# MotorCell_noPow.net
KiCad netlist of a schematic drawn in Altium Designer
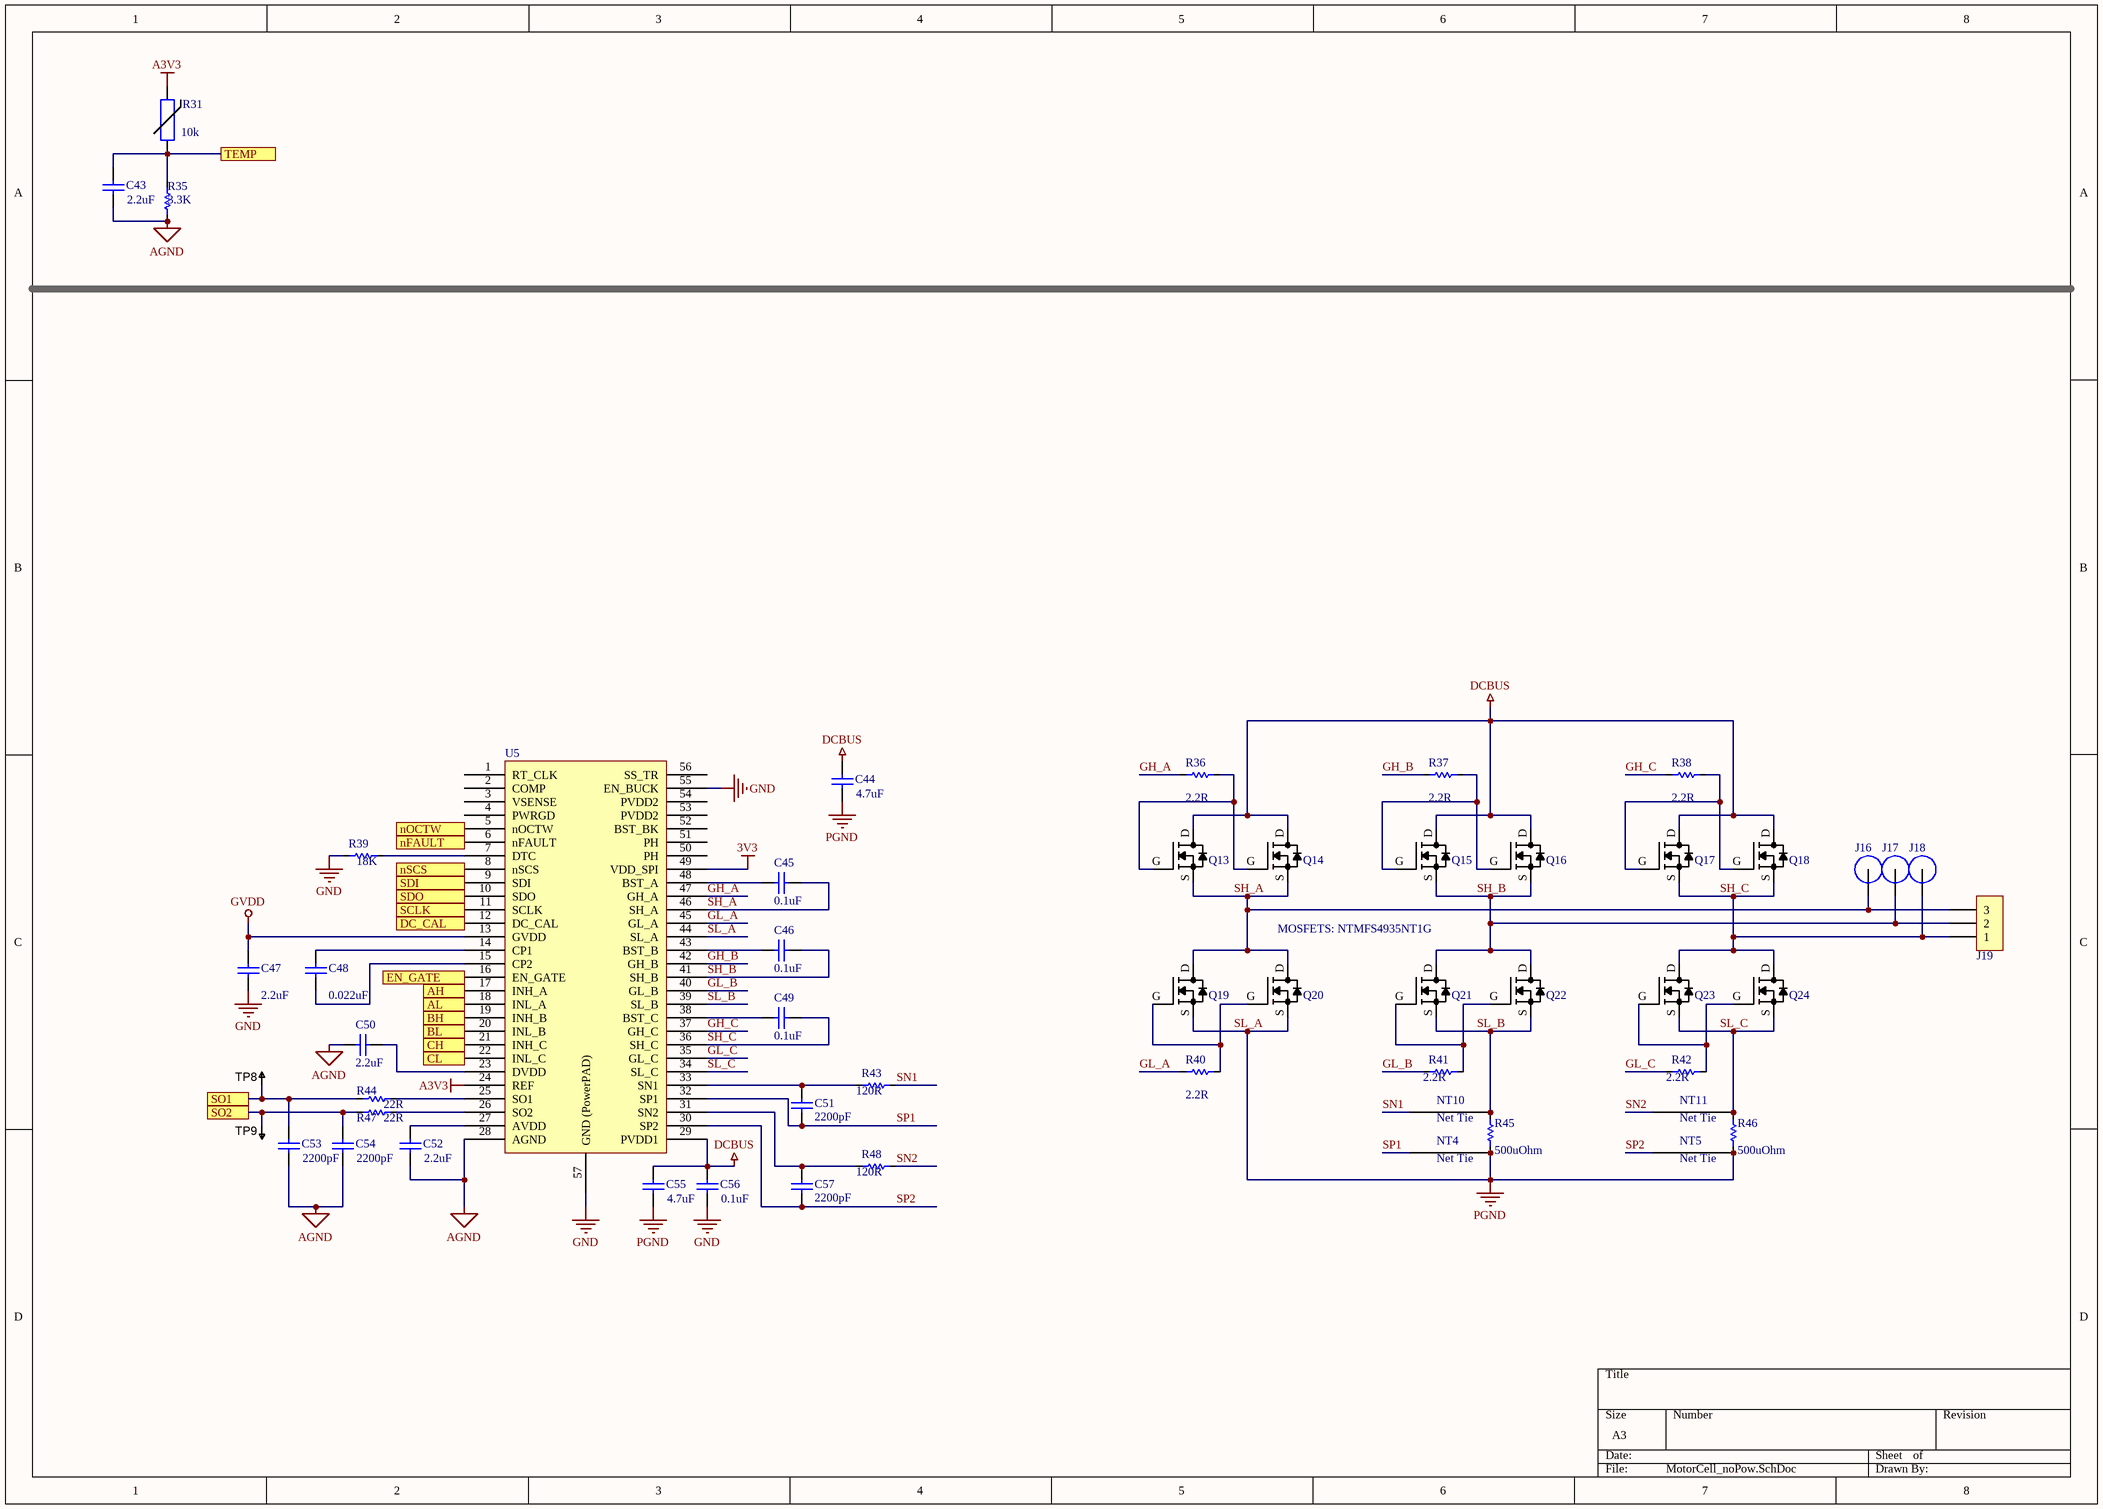
[diagram p0: MotorCell_noPow.SchDoc]

(export (version "E")
  (design (tool "Eeschema 10.0.6"))
  (components
    (comp (ref "C43")
      (value "2.2uF")
      (footprint "C0603")
      (description "Capacitor")
      (fields (field (name "Comment") "Cap") (field (name "PUBLISHER") "Altium Limited"))
      (libsource (lib "Component footprints") (part "Cap"))
    )
    (comp (ref "C44")
      (value "4.7uF")
      (footprint "C0805")
      (description "Capacitor")
      (fields (field (name "Comment") "Cap") (field (name "PUBLISHER") "Altium Limited"))
      (libsource (lib "Component footprints") (part "Cap"))
    )
    (comp (ref "C45")
      (value "0.1uF")
      (footprint "C0603")
      (description "CAP CER 0.1UF 50V X7R 0603")
      (fields (field (name "Comment") "Cap") (field (name "PUBLISHER") "Altium Limited"))
      (libsource (lib "Component footprints") (part "Cap"))
    )
    (comp (ref "C46")
      (value "0.1uF")
      (footprint "C0603")
      (description "CAP CER 0.1UF 50V X7R 0603")
      (fields (field (name "Comment") "Cap") (field (name "PUBLISHER") "Altium Limited"))
      (libsource (lib "Component footprints") (part "Cap"))
    )
    (comp (ref "C47")
      (value "2.2uF")
      (footprint "C0603")
      (description "Capacitor")
      (fields (field (name "Comment") "Cap") (field (name "PUBLISHER") "Altium Limited"))
      (libsource (lib "Component footprints") (part "Cap"))
    )
    (comp (ref "C48")
      (value "0.022uF")
      (footprint "C0603")
      (description "CAP CER 0.022UF 50V X7R 0603")
      (fields (field (name "Comment") "Cap") (field (name "PUBLISHER") "Altium Limited"))
      (libsource (lib "Component footprints") (part "Cap"))
    )
    (comp (ref "C49")
      (value "0.1uF")
      (footprint "C0603")
      (description "CAP CER 0.1UF 50V X7R 0603")
      (fields (field (name "Comment") "Cap") (field (name "PUBLISHER") "Altium Limited"))
      (libsource (lib "Component footprints") (part "Cap"))
    )
    (comp (ref "C50")
      (value "2.2uF")
      (footprint "C0603")
      (description "Capacitor")
      (fields (field (name "Comment") "Cap") (field (name "PUBLISHER") "Altium Limited"))
      (libsource (lib "Component footprints") (part "Cap"))
    )
    (comp (ref "C51")
      (value "2200pF")
      (footprint "C0603")
      (description "CAP CER 2200PF 50V NP0 0603")
      (fields (field (name "Comment") "Cap") (field (name "PUBLISHER") "Altium Limited"))
      (libsource (lib "Component footprints") (part "Cap"))
    )
    (comp (ref "C52")
      (value "2.2uF")
      (footprint "C0603")
      (description "CAP CER 2.2UF 16V X5R 0603")
      (fields (field (name "Comment") "Cap") (field (name "PUBLISHER") "Altium Limited"))
      (libsource (lib "Component footprints") (part "Cap"))
    )
    (comp (ref "C53")
      (value "2200pF")
      (footprint "C0603")
      (description "CAP CER 2200PF 50V NP0 0603")
      (fields (field (name "Comment") "Cap") (field (name "PUBLISHER") "Altium Limited"))
      (libsource (lib "Component footprints") (part "Cap"))
    )
    (comp (ref "C54")
      (value "2200pF")
      (footprint "C0603")
      (description "CAP CER 2200PF 50V NP0 0603")
      (fields (field (name "Comment") "Cap") (field (name "PUBLISHER") "Altium Limited"))
      (libsource (lib "Component footprints") (part "Cap"))
    )
    (comp (ref "C55")
      (value "4.7uF")
      (footprint "C0805")
      (description "CAP CER 4.7UF 35V X5R 0805")
      (fields (field (name "Comment") "Cap") (field (name "PUBLISHER") "Altium Limited"))
      (libsource (lib "Component footprints") (part "Cap"))
    )
    (comp (ref "C56")
      (value "0.1uF")
      (footprint "C0603")
      (description "CAP CER 0.1UF 50V X7R 0603")
      (fields (field (name "Comment") "Cap") (field (name "PUBLISHER") "Altium Limited"))
      (libsource (lib "Component footprints") (part "Cap"))
    )
    (comp (ref "C57")
      (value "2200pF")
      (footprint "C0603")
      (description "CAP CER 2200PF 50V NP0 0603")
      (fields (field (name "Comment") "Cap") (field (name "PUBLISHER") "Altium Limited"))
      (libsource (lib "Component footprints") (part "Cap"))
    )
    (comp (ref "J16")
      (value "~")
      (footprint "M3 Spade Hole")
      (description "M3 Spade Terminal")
      (libsource (lib "CustomComponents") (part "M3 Spade Terminal"))
    )
    (comp (ref "J17")
      (value "~")
      (footprint "M3 Spade Hole")
      (description "M3 Spade Terminal")
      (libsource (lib "CustomComponents") (part "M3 Spade Terminal"))
    )
    (comp (ref "J18")
      (value "~")
      (footprint "M3 Spade Hole")
      (description "M3 Spade Terminal")
      (libsource (lib "CustomComponents") (part "M3 Spade Terminal"))
    )
    (comp (ref "J19")
      (value "1704936")
      (footprint "1704936")
      (description "CONN TERM BLOCK 3POS 7.62MM")
      (fields (field (name "MANUFACTURER") "Phoenix Contact") (field (name "VOLTAGE") "300V"))
      (libsource (lib "CustomComponents") (part "1704936"))
    )
    (comp (ref "NT4")
      (value "0.25mm")
      (footprint "NetTie_0.25mm")
      (libsource (lib "CustomComponents") (part "NetTie_0.25mm"))
    )
    (comp (ref "NT5")
      (value "0.25mm")
      (footprint "NetTie_0.25mm")
      (libsource (lib "CustomComponents") (part "NetTie_0.25mm"))
    )
    (comp (ref "NT10")
      (value "0.25mm")
      (footprint "NetTie_0.25mm")
      (libsource (lib "CustomComponents") (part "NetTie_0.25mm"))
    )
    (comp (ref "NT11")
      (value "0.25mm")
      (footprint "NetTie_0.25mm")
      (libsource (lib "CustomComponents") (part "NetTie_0.25mm"))
    )
    (comp (ref "Q13")
      (value "~")
      (footprint "SO8FL")
      (description "MOSFET N-CH 30V 13A SO8FL")
      (fields
        (field (name "MANUFACTURER") "ON Semiconductor")
        (field (name "MANUFACTURER PART NUMBER") "NTMFS4935NT1G")
      )
      (libsource (lib "CustomComponents") (part "NTMFS4935NT1G"))
    )
    (comp (ref "Q14")
      (value "FILL_FOOTPRINT")
      (footprint "SO8FL_FILL")
      (description "MOSFET N-CH 30V 13A SO8FL")
      (fields
        (field (name "MANUFACTURER") "ON Semiconductor")
        (field (name "MANUFACTURER PART NUMBER") "NTMFS4935NT1G")
      )
      (libsource (lib "CustomComponents") (part "NTMFS4935NT1G"))
    )
    (comp (ref "Q15")
      (value "~")
      (footprint "SO8FL")
      (description "MOSFET N-CH 30V 13A SO8FL")
      (fields
        (field (name "MANUFACTURER") "ON Semiconductor")
        (field (name "MANUFACTURER PART NUMBER") "NTMFS4935NT1G")
      )
      (libsource (lib "CustomComponents") (part "NTMFS4935NT1G"))
    )
    (comp (ref "Q16")
      (value "FILL_FOOTPRINT")
      (footprint "SO8FL_FILL")
      (description "MOSFET N-CH 30V 13A SO8FL")
      (fields
        (field (name "MANUFACTURER") "ON Semiconductor")
        (field (name "MANUFACTURER PART NUMBER") "NTMFS4935NT1G")
      )
      (libsource (lib "CustomComponents") (part "NTMFS4935NT1G"))
    )
    (comp (ref "Q17")
      (value "~")
      (footprint "SO8FL")
      (description "MOSFET N-CH 30V 13A SO8FL")
      (fields
        (field (name "MANUFACTURER") "ON Semiconductor")
        (field (name "MANUFACTURER PART NUMBER") "NTMFS4935NT1G")
      )
      (libsource (lib "CustomComponents") (part "NTMFS4935NT1G"))
    )
    (comp (ref "Q18")
      (value "FILL_FOOTPRINT")
      (footprint "SO8FL_FILL")
      (description "MOSFET N-CH 30V 13A SO8FL")
      (fields
        (field (name "MANUFACTURER") "ON Semiconductor")
        (field (name "MANUFACTURER PART NUMBER") "NTMFS4935NT1G")
      )
      (libsource (lib "CustomComponents") (part "NTMFS4935NT1G"))
    )
    (comp (ref "Q19")
      (value "~")
      (footprint "SO8FL")
      (description "MOSFET N-CH 30V 13A SO8FL")
      (fields
        (field (name "MANUFACTURER") "ON Semiconductor")
        (field (name "MANUFACTURER PART NUMBER") "NTMFS4935NT1G")
      )
      (libsource (lib "CustomComponents") (part "NTMFS4935NT1G"))
    )
    (comp (ref "Q20")
      (value "~")
      (footprint "SO8FL")
      (description "MOSFET N-CH 30V 13A SO8FL")
      (fields
        (field (name "MANUFACTURER") "ON Semiconductor")
        (field (name "MANUFACTURER PART NUMBER") "NTMFS4935NT1G")
      )
      (libsource (lib "CustomComponents") (part "NTMFS4935NT1G"))
    )
    (comp (ref "Q21")
      (value "~")
      (footprint "SO8FL")
      (description "MOSFET N-CH 30V 13A SO8FL")
      (fields
        (field (name "MANUFACTURER") "ON Semiconductor")
        (field (name "MANUFACTURER PART NUMBER") "NTMFS4935NT1G")
      )
      (libsource (lib "CustomComponents") (part "NTMFS4935NT1G"))
    )
    (comp (ref "Q22")
      (value "~")
      (footprint "SO8FL")
      (description "MOSFET N-CH 30V 13A SO8FL")
      (fields
        (field (name "MANUFACTURER") "ON Semiconductor")
        (field (name "MANUFACTURER PART NUMBER") "NTMFS4935NT1G")
      )
      (libsource (lib "CustomComponents") (part "NTMFS4935NT1G"))
    )
    (comp (ref "Q23")
      (value "~")
      (footprint "SO8FL")
      (description "MOSFET N-CH 30V 13A SO8FL")
      (fields
        (field (name "MANUFACTURER") "ON Semiconductor")
        (field (name "MANUFACTURER PART NUMBER") "NTMFS4935NT1G")
      )
      (libsource (lib "CustomComponents") (part "NTMFS4935NT1G"))
    )
    (comp (ref "Q24")
      (value "~")
      (footprint "SO8FL")
      (description "MOSFET N-CH 30V 13A SO8FL")
      (fields
        (field (name "MANUFACTURER") "ON Semiconductor")
        (field (name "MANUFACTURER PART NUMBER") "NTMFS4935NT1G")
      )
      (libsource (lib "CustomComponents") (part "NTMFS4935NT1G"))
    )
    (comp (ref "R31")
      (value "10k")
      (footprint "RESC1005X40N")
      (description "THERMISTOR 10K OHM NTC 0402 SMD")
      (libsource (lib "CustomComponents") (part "NCP15XH103F03RC"))
    )
    (comp (ref "R35")
      (value "3.3K")
      (footprint "R0603")
      (description "Resistor")
      (fields (field (name "Comment") "Res") (field (name "PUBLISHER") "Altium Limited"))
      (libsource (lib "Component footprints") (part "Res"))
    )
    (comp (ref "R36")
      (value "2.2R")
      (footprint "R0603")
      (description "Resistor")
      (fields (field (name "Comment") "Res") (field (name "PUBLISHER") "Altium Limited"))
      (libsource (lib "Component footprints") (part "Res"))
    )
    (comp (ref "R37")
      (value "2.2R")
      (footprint "R0603")
      (description "Resistor")
      (fields (field (name "Comment") "Res") (field (name "PUBLISHER") "Altium Limited"))
      (libsource (lib "Component footprints") (part "Res"))
    )
    (comp (ref "R38")
      (value "2.2R")
      (footprint "R0603")
      (description "Resistor")
      (fields (field (name "Comment") "Res") (field (name "PUBLISHER") "Altium Limited"))
      (libsource (lib "Component footprints") (part "Res"))
    )
    (comp (ref "R39")
      (value "18K")
      (footprint "R0603")
      (description "Resistor")
      (fields (field (name "Comment") "Res") (field (name "PUBLISHER") "Altium Limited"))
      (libsource (lib "Component footprints") (part "Res"))
    )
    (comp (ref "R40")
      (value "2.2R")
      (footprint "R0603")
      (description "Resistor")
      (fields (field (name "Comment") "Res") (field (name "PUBLISHER") "Altium Limited"))
      (libsource (lib "Component footprints") (part "Res"))
    )
    (comp (ref "R41")
      (value "2.2R")
      (footprint "R0603")
      (description "Resistor")
      (fields (field (name "Comment") "Res") (field (name "PUBLISHER") "Altium Limited"))
      (libsource (lib "Component footprints") (part "Res"))
    )
    (comp (ref "R42")
      (value "2.2R")
      (footprint "R0603")
      (description "Resistor")
      (fields (field (name "Comment") "Res") (field (name "PUBLISHER") "Altium Limited"))
      (libsource (lib "Component footprints") (part "Res"))
    )
    (comp (ref "R43")
      (value "120R")
      (footprint "R0603")
      (description "Resistor")
      (fields (field (name "Comment") "Res") (field (name "PUBLISHER") "Altium Limited"))
      (libsource (lib "Component footprints") (part "Res"))
    )
    (comp (ref "R44")
      (value "22R")
      (footprint "R0603")
      (description "Resistor")
      (fields (field (name "Comment") "Res") (field (name "PUBLISHER") "Altium Limited"))
      (libsource (lib "Component footprints") (part "Res"))
    )
    (comp (ref "R45")
      (value "500uOhm")
      (footprint "R2512")
      (description "RES SMD 0.0005 OHM 1% 3W 2512")
      (fields (field (name "Comment") "Res") (field (name "PUBLISHER") "Altium Limited"))
      (libsource (lib "Component footprints") (part "Res"))
    )
    (comp (ref "R46")
      (value "500uOhm")
      (footprint "R2512")
      (description "RES SMD 0.0005 OHM 1% 3W 2512")
      (fields (field (name "Comment") "Res") (field (name "PUBLISHER") "Altium Limited"))
      (libsource (lib "Component footprints") (part "Res"))
    )
    (comp (ref "R47")
      (value "22R")
      (footprint "R0603")
      (description "Resistor")
      (fields (field (name "Comment") "Res") (field (name "PUBLISHER") "Altium Limited"))
      (libsource (lib "Component footprints") (part "Res"))
    )
    (comp (ref "R48")
      (value "120R")
      (footprint "R0603")
      (description "Resistor")
      (fields (field (name "Comment") "Res") (field (name "PUBLISHER") "Altium Limited"))
      (libsource (lib "Component footprints") (part "Res"))
    )
    (comp (ref "TP8")
      (value "TESTPOINT")
      (footprint "TP-R30")
      (description "SMD test pin")
      (libsource (lib "PBL - Test Points") (part "TESTPOINT"))
    )
    (comp (ref "TP9")
      (value "TESTPOINT")
      (footprint "TP-R30")
      (description "SMD test pin")
      (libsource (lib "PBL - Test Points") (part "TESTPOINT"))
    )
    (comp (ref "U5")
      (value "~")
      (footprint "TSSOP50P810X120_HS-57N")
      (description "MOTOR DRIVER, 3PH, 56HTSSOP")
      (libsource (lib "CustomComponents") (part "DRV8301"))
    )
  )
  (nets
    (net (code "1") (name "/AH") (class "Default")
      (node (ref "U5") (pin "17") (pinfunction "INH_A_17") (pintype "passive"))
    )
    (net (code "2") (name "/AL") (class "Default")
      (node (ref "U5") (pin "18") (pinfunction "INL_A_18") (pintype "passive"))
    )
    (net (code "3") (name "/BH") (class "Default")
      (node (ref "U5") (pin "19") (pinfunction "INH_B_19") (pintype "passive"))
    )
    (net (code "4") (name "/BL") (class "Default")
      (node (ref "U5") (pin "20") (pinfunction "INL_B_20") (pintype "passive"))
    )
    (net (code "5") (name "/CH") (class "Default")
      (node (ref "U5") (pin "21") (pinfunction "INH_C_21") (pintype "passive"))
    )
    (net (code "6") (name "/CL") (class "Default")
      (node (ref "U5") (pin "22") (pinfunction "INL_C_22") (pintype "passive"))
    )
    (net (code "7") (name "/DC_CAL") (class "Default")
      (node (ref "U5") (pin "12") (pinfunction "DC_CAL_12") (pintype "passive"))
    )
    (net (code "8") (name "/EN_GATE") (class "Default")
      (node (ref "U5") (pin "16") (pinfunction "EN_GATE_16") (pintype "passive"))
    )
    (net (code "9") (name "/GH_A") (class "Default")
      (node (ref "R36") (pin "2") (pinfunction "2_2") (pintype "passive"))
      (node (ref "U5") (pin "47") (pinfunction "GH_A_47") (pintype "passive"))
    )
    (net (code "10") (name "/GH_B") (class "Default")
      (node (ref "R37") (pin "2") (pinfunction "2_2") (pintype "passive"))
      (node (ref "U5") (pin "42") (pinfunction "GH_B_42") (pintype "passive"))
    )
    (net (code "11") (name "/GH_C") (class "Default")
      (node (ref "R38") (pin "2") (pinfunction "2_2") (pintype "passive"))
      (node (ref "U5") (pin "37") (pinfunction "GH_C_37") (pintype "passive"))
    )
    (net (code "12") (name "/GL_A") (class "Default")
      (node (ref "R40") (pin "2") (pinfunction "2_2") (pintype "passive"))
      (node (ref "U5") (pin "45") (pinfunction "GL_A_45") (pintype "passive"))
    )
    (net (code "13") (name "/GL_B") (class "Default")
      (node (ref "R41") (pin "2") (pinfunction "2_2") (pintype "passive"))
      (node (ref "U5") (pin "40") (pinfunction "GL_B_40") (pintype "passive"))
    )
    (net (code "14") (name "/GL_C") (class "Default")
      (node (ref "R42") (pin "2") (pinfunction "2_2") (pintype "passive"))
      (node (ref "U5") (pin "35") (pinfunction "GL_C_35") (pintype "passive"))
    )
    (net (code "15") (name "/SCLK") (class "Default")
      (node (ref "U5") (pin "11") (pinfunction "SCLK_11") (pintype "passive"))
    )
    (net (code "16") (name "/SDI") (class "Default")
      (node (ref "U5") (pin "9") (pinfunction "SDI_9") (pintype "passive"))
    )
    (net (code "17") (name "/SDO") (class "Default")
      (node (ref "U5") (pin "10") (pinfunction "SDO_10") (pintype "passive"))
    )
    (net (code "18") (name "/SH_A") (class "Default")
      (node (ref "C45") (pin "1") (pinfunction "1_1") (pintype "passive"))
      (node (ref "J16") (pin "1") (pinfunction "1_1") (pintype "passive"))
      (node (ref "J19") (pin "3") (pinfunction "3_3") (pintype "passive"))
      (node (ref "Q13") (pin "S") (pinfunction "S_S") (pintype "passive"))
      (node (ref "Q14") (pin "S") (pinfunction "S_S") (pintype "passive"))
      (node (ref "Q19") (pin "D") (pinfunction "D_D") (pintype "passive"))
      (node (ref "Q20") (pin "D") (pinfunction "D_D") (pintype "passive"))
      (node (ref "U5") (pin "46") (pinfunction "SH_A_46") (pintype "passive"))
    )
    (net (code "19") (name "/SH_B") (class "Default")
      (node (ref "C46") (pin "1") (pinfunction "1_1") (pintype "passive"))
      (node (ref "J17") (pin "1") (pinfunction "1_1") (pintype "passive"))
      (node (ref "J19") (pin "2") (pinfunction "2_2") (pintype "passive"))
      (node (ref "Q15") (pin "S") (pinfunction "S_S") (pintype "passive"))
      (node (ref "Q16") (pin "S") (pinfunction "S_S") (pintype "passive"))
      (node (ref "Q21") (pin "D") (pinfunction "D_D") (pintype "passive"))
      (node (ref "Q22") (pin "D") (pinfunction "D_D") (pintype "passive"))
      (node (ref "U5") (pin "41") (pinfunction "SH_B_41") (pintype "passive"))
    )
    (net (code "20") (name "/SH_C") (class "Default")
      (node (ref "C49") (pin "1") (pinfunction "1_1") (pintype "passive"))
      (node (ref "J18") (pin "1") (pinfunction "1_1") (pintype "passive"))
      (node (ref "J19") (pin "1") (pinfunction "1_1") (pintype "passive"))
      (node (ref "Q17") (pin "S") (pinfunction "S_S") (pintype "passive"))
      (node (ref "Q18") (pin "S") (pinfunction "S_S") (pintype "passive"))
      (node (ref "Q23") (pin "D") (pinfunction "D_D") (pintype "passive"))
      (node (ref "Q24") (pin "D") (pinfunction "D_D") (pintype "passive"))
      (node (ref "U5") (pin "36") (pinfunction "SH_C_36") (pintype "passive"))
    )
    (net (code "21") (name "/SL_B") (class "Default")
      (node (ref "NT10") (pin "2") (pintype "passive"))
      (node (ref "Q21") (pin "S") (pinfunction "S_S") (pintype "passive"))
      (node (ref "Q22") (pin "S") (pinfunction "S_S") (pintype "passive"))
      (node (ref "R45") (pin "2") (pinfunction "2_2") (pintype "passive"))
      (node (ref "U5") (pin "39") (pinfunction "SL_B_39") (pintype "passive"))
    )
    (net (code "22") (name "/SL_C") (class "Default")
      (node (ref "NT11") (pin "2") (pintype "passive"))
      (node (ref "Q23") (pin "S") (pinfunction "S_S") (pintype "passive"))
      (node (ref "Q24") (pin "S") (pinfunction "S_S") (pintype "passive"))
      (node (ref "R46") (pin "2") (pinfunction "2_2") (pintype "passive"))
      (node (ref "U5") (pin "34") (pinfunction "SL_C_34") (pintype "passive"))
    )
    (net (code "23") (name "/SN1") (class "Default")
      (node (ref "NT10") (pin "1") (pintype "passive"))
      (node (ref "R43") (pin "2") (pinfunction "2_2") (pintype "passive"))
    )
    (net (code "24") (name "/SN2") (class "Default")
      (node (ref "NT11") (pin "1") (pintype "passive"))
      (node (ref "R48") (pin "2") (pinfunction "2_2") (pintype "passive"))
    )
    (net (code "25") (name "/SO1") (class "Default")
      (node (ref "C53") (pin "2") (pinfunction "2_2") (pintype "passive"))
      (node (ref "R44") (pin "1") (pinfunction "1_1") (pintype "passive"))
      (node (ref "TP8") (pin "1") (pintype "passive"))
    )
    (net (code "26") (name "/SO2") (class "Default")
      (node (ref "C54") (pin "2") (pinfunction "2_2") (pintype "passive"))
      (node (ref "R47") (pin "1") (pinfunction "1_1") (pintype "passive"))
      (node (ref "TP9") (pin "1") (pintype "passive"))
    )
    (net (code "27") (name "/SP1") (class "Default")
      (node (ref "C51") (pin "2") (pinfunction "2_2") (pintype "passive"))
      (node (ref "NT4") (pin "1") (pintype "passive"))
      (node (ref "U5") (pin "32") (pinfunction "SP1_32") (pintype "passive"))
    )
    (net (code "28") (name "/SP2") (class "Default")
      (node (ref "C57") (pin "2") (pinfunction "2_2") (pintype "passive"))
      (node (ref "NT5") (pin "1") (pintype "passive"))
      (node (ref "U5") (pin "30") (pinfunction "SP2_30") (pintype "passive"))
    )
    (net (code "29") (name "/TEMP") (class "Default")
      (node (ref "C43") (pin "2") (pinfunction "2_2") (pintype "passive"))
      (node (ref "R31") (pin "1") (pinfunction "0_1") (pintype "passive"))
      (node (ref "R35") (pin "2") (pinfunction "2_2") (pintype "passive"))
    )
    (net (code "30") (name "/nFAULT") (class "Default")
      (node (ref "U5") (pin "6") (pinfunction "nFAULT_6") (pintype "passive"))
    )
    (net (code "31") (name "/nOCTW") (class "Default")
      (node (ref "U5") (pin "5") (pinfunction "nOCTW_5") (pintype "passive"))
    )
    (net (code "32") (name "/nSCS") (class "Default")
      (node (ref "U5") (pin "8") (pinfunction "nSCS_8") (pintype "passive"))
    )
    (net (code "33") (name "3V3") (class "Default")
      (node (ref "U5") (pin "49") (pinfunction "VDD_SPI_49") (pintype "passive"))
    )
    (net (code "34") (name "A3V3") (class "Default")
      (node (ref "R31") (pin "2") (pinfunction "0_2") (pintype "passive"))
      (node (ref "U5") (pin "24") (pinfunction "REF_24") (pintype "passive"))
    )
    (net (code "35") (name "AGND") (class "Default")
      (node (ref "C43") (pin "1") (pinfunction "1_1") (pintype "passive"))
      (node (ref "C50") (pin "2") (pinfunction "2_2") (pintype "passive"))
      (node (ref "C52") (pin "1") (pinfunction "1_1") (pintype "passive"))
      (node (ref "C53") (pin "1") (pinfunction "1_1") (pintype "passive"))
      (node (ref "C54") (pin "1") (pinfunction "1_1") (pintype "passive"))
      (node (ref "R35") (pin "1") (pinfunction "1_1") (pintype "passive"))
      (node (ref "U5") (pin "28") (pinfunction "AGND_28") (pintype "passive"))
    )
    (net (code "36") (name "DCBUS") (class "Default")
      (node (ref "C44") (pin "2") (pinfunction "2_2") (pintype "passive"))
      (node (ref "C55") (pin "2") (pinfunction "2_2") (pintype "passive"))
      (node (ref "C56") (pin "2") (pinfunction "2_2") (pintype "passive"))
      (node (ref "Q13") (pin "D") (pinfunction "D_D") (pintype "passive"))
      (node (ref "Q14") (pin "D") (pinfunction "D_D") (pintype "passive"))
      (node (ref "Q15") (pin "D") (pinfunction "D_D") (pintype "passive"))
      (node (ref "Q16") (pin "D") (pinfunction "D_D") (pintype "passive"))
      (node (ref "Q17") (pin "D") (pinfunction "D_D") (pintype "passive"))
      (node (ref "Q18") (pin "D") (pinfunction "D_D") (pintype "passive"))
      (node (ref "U5") (pin "29") (pinfunction "PVDD1_29") (pintype "passive"))
    )
    (net (code "37") (name "GND") (class "Default")
      (node (ref "C47") (pin "1") (pinfunction "1_1") (pintype "passive"))
      (node (ref "C56") (pin "1") (pinfunction "1_1") (pintype "passive"))
      (node (ref "R39") (pin "1") (pinfunction "1_1") (pintype "passive"))
      (node (ref "U5") (pin "55") (pinfunction "EN_BUCK_55") (pintype "passive"))
      (node (ref "U5") (pin "57") (pinfunction "GND_(PowerPAD)_57") (pintype "passive"))
    )
    (net (code "38") (name "GVDD") (class "Default")
      (node (ref "C47") (pin "2") (pinfunction "2_2") (pintype "passive"))
      (node (ref "U5") (pin "13") (pinfunction "GVDD_13") (pintype "passive"))
    )
    (net (code "39") (name "Net-(Q13-PadG)") (class "Default")
      (node (ref "Q13") (pin "G") (pinfunction "G_G") (pintype "passive"))
      (node (ref "Q14") (pin "G") (pinfunction "G_G") (pintype "passive"))
      (node (ref "R36") (pin "1") (pinfunction "1_1") (pintype "passive"))
    )
    (net (code "40") (name "Net-(Q15-PadG)") (class "Default")
      (node (ref "Q15") (pin "G") (pinfunction "G_G") (pintype "passive"))
      (node (ref "Q16") (pin "G") (pinfunction "G_G") (pintype "passive"))
      (node (ref "R37") (pin "1") (pinfunction "1_1") (pintype "passive"))
    )
    (net (code "41") (name "Net-(Q17-PadG)") (class "Default")
      (node (ref "Q17") (pin "G") (pinfunction "G_G") (pintype "passive"))
      (node (ref "Q18") (pin "G") (pinfunction "G_G") (pintype "passive"))
      (node (ref "R38") (pin "1") (pinfunction "1_1") (pintype "passive"))
    )
    (net (code "42") (name "Net-(Q19-PadG)") (class "Default")
      (node (ref "Q19") (pin "G") (pinfunction "G_G") (pintype "passive"))
      (node (ref "Q20") (pin "G") (pinfunction "G_G") (pintype "passive"))
      (node (ref "R40") (pin "1") (pinfunction "1_1") (pintype "passive"))
    )
    (net (code "43") (name "Net-(Q21-PadG)") (class "Default")
      (node (ref "Q21") (pin "G") (pinfunction "G_G") (pintype "passive"))
      (node (ref "Q22") (pin "G") (pinfunction "G_G") (pintype "passive"))
      (node (ref "R41") (pin "1") (pinfunction "1_1") (pintype "passive"))
    )
    (net (code "44") (name "Net-(Q23-PadG)") (class "Default")
      (node (ref "Q23") (pin "G") (pinfunction "G_G") (pintype "passive"))
      (node (ref "Q24") (pin "G") (pinfunction "G_G") (pintype "passive"))
      (node (ref "R42") (pin "1") (pinfunction "1_1") (pintype "passive"))
    )
    (net (code "45") (name "Net-(U5-AVDD)") (class "Default")
      (node (ref "C52") (pin "2") (pinfunction "2_2") (pintype "passive"))
      (node (ref "U5") (pin "27") (pinfunction "AVDD_27") (pintype "passive"))
    )
    (net (code "46") (name "Net-(U5-BST_A)") (class "Default")
      (node (ref "C45") (pin "2") (pinfunction "2_2") (pintype "passive"))
      (node (ref "U5") (pin "48") (pinfunction "BST_A_48") (pintype "passive"))
    )
    (net (code "47") (name "Net-(U5-BST_B)") (class "Default")
      (node (ref "C46") (pin "2") (pinfunction "2_2") (pintype "passive"))
      (node (ref "U5") (pin "43") (pinfunction "BST_B_43") (pintype "passive"))
    )
    (net (code "48") (name "Net-(U5-BST_C)") (class "Default")
      (node (ref "C49") (pin "2") (pinfunction "2_2") (pintype "passive"))
      (node (ref "U5") (pin "38") (pinfunction "BST_C_38") (pintype "passive"))
    )
    (net (code "49") (name "Net-(U5-CP1)") (class "Default")
      (node (ref "C48") (pin "2") (pinfunction "2_2") (pintype "passive"))
      (node (ref "U5") (pin "14") (pinfunction "CP1_14") (pintype "passive"))
    )
    (net (code "50") (name "Net-(U5-CP2)") (class "Default")
      (node (ref "C48") (pin "1") (pinfunction "1_1") (pintype "passive"))
      (node (ref "U5") (pin "15") (pinfunction "CP2_15") (pintype "passive"))
    )
    (net (code "51") (name "Net-(U5-DTC)") (class "Default")
      (node (ref "R39") (pin "2") (pinfunction "2_2") (pintype "passive"))
      (node (ref "U5") (pin "7") (pinfunction "DTC_7") (pintype "passive"))
    )
    (net (code "52") (name "Net-(U5-DVDD)") (class "Default")
      (node (ref "C50") (pin "1") (pinfunction "1_1") (pintype "passive"))
      (node (ref "U5") (pin "23") (pinfunction "DVDD_23") (pintype "passive"))
    )
    (net (code "53") (name "Net-(U5-SN1)") (class "Default")
      (node (ref "C51") (pin "1") (pinfunction "1_1") (pintype "passive"))
      (node (ref "R43") (pin "1") (pinfunction "1_1") (pintype "passive"))
      (node (ref "U5") (pin "33") (pinfunction "SN1_33") (pintype "passive"))
    )
    (net (code "54") (name "Net-(U5-SN2)") (class "Default")
      (node (ref "C57") (pin "1") (pinfunction "1_1") (pintype "passive"))
      (node (ref "R48") (pin "1") (pinfunction "1_1") (pintype "passive"))
      (node (ref "U5") (pin "31") (pinfunction "SN2_31") (pintype "passive"))
    )
    (net (code "55") (name "Net-(U5-SO1)") (class "Default")
      (node (ref "R44") (pin "2") (pinfunction "2_2") (pintype "passive"))
      (node (ref "U5") (pin "25") (pinfunction "SO1_25") (pintype "passive"))
    )
    (net (code "56") (name "Net-(U5-SO2)") (class "Default")
      (node (ref "R47") (pin "2") (pinfunction "2_2") (pintype "passive"))
      (node (ref "U5") (pin "26") (pinfunction "SO2_26") (pintype "passive"))
    )
    (net (code "57") (name "PGND") (class "Default")
      (node (ref "C44") (pin "1") (pinfunction "1_1") (pintype "passive"))
      (node (ref "C55") (pin "1") (pinfunction "1_1") (pintype "passive"))
      (node (ref "NT4") (pin "2") (pintype "passive"))
      (node (ref "NT5") (pin "2") (pintype "passive"))
      (node (ref "Q19") (pin "S") (pinfunction "S_S") (pintype "passive"))
      (node (ref "Q20") (pin "S") (pinfunction "S_S") (pintype "passive"))
      (node (ref "R45") (pin "1") (pinfunction "1_1") (pintype "passive"))
      (node (ref "R46") (pin "1") (pinfunction "1_1") (pintype "passive"))
      (node (ref "U5") (pin "44") (pinfunction "SL_A_44") (pintype "passive"))
    )
    (net (code "58") (name "unconnected-(U5-BST_BK-Pad52)") (class "Default")
      (node (ref "U5") (pin "52") (pinfunction "BST_BK_52") (pintype "passive"))
    )
    (net (code "59") (name "unconnected-(U5-COMP-Pad2)") (class "Default")
      (node (ref "U5") (pin "2") (pinfunction "COMP_2") (pintype "passive"))
    )
    (net (code "60") (name "unconnected-(U5-PH-Pad50)") (class "Default")
      (node (ref "U5") (pin "50") (pinfunction "PH_50") (pintype "passive"))
    )
    (net (code "61") (name "unconnected-(U5-PH-Pad51)") (class "Default")
      (node (ref "U5") (pin "51") (pinfunction "PH_51") (pintype "passive"))
    )
    (net (code "62") (name "unconnected-(U5-PVDD2-Pad53)") (class "Default")
      (node (ref "U5") (pin "53") (pinfunction "PVDD2_53") (pintype "passive"))
    )
    (net (code "63") (name "unconnected-(U5-PVDD2-Pad54)") (class "Default")
      (node (ref "U5") (pin "54") (pinfunction "PVDD2_54") (pintype "passive"))
    )
    (net (code "64") (name "unconnected-(U5-PWRGD-Pad4)") (class "Default")
      (node (ref "U5") (pin "4") (pinfunction "PWRGD_4") (pintype "passive"))
    )
    (net (code "65") (name "unconnected-(U5-RT_CLK-Pad1)") (class "Default")
      (node (ref "U5") (pin "1") (pinfunction "RT_CLK_1") (pintype "passive"))
    )
    (net (code "66") (name "unconnected-(U5-SS_TR-Pad56)") (class "Default")
      (node (ref "U5") (pin "56") (pinfunction "SS_TR_56") (pintype "passive"))
    )
    (net (code "67") (name "unconnected-(U5-VSENSE-Pad3)") (class "Default")
      (node (ref "U5") (pin "3") (pinfunction "VSENSE_3") (pintype "passive"))
    )
  )
)
